# TurquoiseBicuspidProgrammer.net
KiCad netlist of a schematic drawn in EAGLE
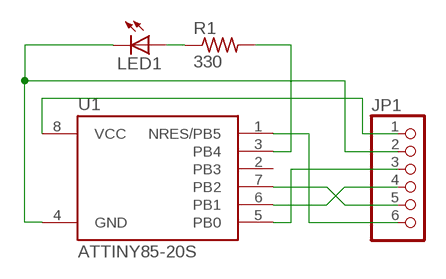
[diagram p0: schematic, sheet 1]

(export (version "E")
  (design (tool "Eeschema 10.0.6"))
  (components
    (comp (ref "JP1")
      (value "PINHD-1X6")
      (footprint "eagle-import:1X06")
      (libsource (lib "eagle-import") (part "PINHD-1X6"))
    )
    (comp (ref "LED1")
      (value "LED5MM")
      (footprint "eagle-import:LED5MM")
      (libsource (lib "eagle-import") (part "LED5MM"))
    )
    (comp (ref "R1")
      (value "330")
      (footprint "eagle-import:0207_10")
      (libsource (lib "eagle-import") (part "R-US_0207/10"))
    )
    (comp (ref "U1")
      (value "ATTINY85-20S")
      (footprint "eagle-import:SOIC8_EIAJ_208MIL")
      (libsource (lib "eagle-import") (part "ATTINY85S-20"))
    )
  )
  (nets
    (net (code "1") (name "Net-(LED1-C)") (class "Default")
      (node (ref "JP1") (pin "2") (pinfunction "2_2") (pintype "passive"))
      (node (ref "LED1") (pin "K") (pinfunction "C_K") (pintype "passive"))
      (node (ref "U1") (pin "4") (pinfunction "GND_4") (pintype "power_in"))
    )
    (net (code "2") (name "Net-(LED1-PadA)") (class "Default")
      (node (ref "LED1") (pin "A") (pinfunction "A_A") (pintype "passive"))
      (node (ref "R1") (pin "1") (pinfunction "1_1") (pintype "passive"))
    )
    (net (code "3") (name "Net-(U1-NRES{slash}PB5)") (class "Default")
      (node (ref "JP1") (pin "6") (pinfunction "6_6") (pintype "passive"))
      (node (ref "U1") (pin "1") (pinfunction "NRES/PB5_1") (pintype "bidirectional"))
    )
    (net (code "4") (name "Net-(U1-PB0)") (class "Default")
      (node (ref "JP1") (pin "3") (pinfunction "3_3") (pintype "passive"))
      (node (ref "U1") (pin "5") (pinfunction "PB0_5") (pintype "bidirectional"))
    )
    (net (code "5") (name "Net-(U1-PB1)") (class "Default")
      (node (ref "JP1") (pin "4") (pinfunction "4_4") (pintype "passive"))
      (node (ref "U1") (pin "6") (pinfunction "PB1_6") (pintype "bidirectional"))
    )
    (net (code "6") (name "Net-(U1-PB2)") (class "Default")
      (node (ref "JP1") (pin "5") (pinfunction "5_5") (pintype "passive"))
      (node (ref "U1") (pin "7") (pinfunction "PB2_7") (pintype "bidirectional"))
    )
    (net (code "7") (name "Net-(U1-PB4)") (class "Default")
      (node (ref "R1") (pin "2") (pinfunction "2_2") (pintype "passive"))
      (node (ref "U1") (pin "3") (pinfunction "PB4_3") (pintype "bidirectional"))
    )
    (net (code "8") (name "Net-(U1-VCC)") (class "Default")
      (node (ref "JP1") (pin "1") (pinfunction "1_1") (pintype "passive"))
      (node (ref "U1") (pin "8") (pinfunction "VCC_8") (pintype "power_in"))
    )
    (net (code "9") (name "unconnected-(U1-PB3-Pad2)") (class "Default")
      (node (ref "U1") (pin "2") (pinfunction "PB3_2") (pintype "bidirectional"))
    )
  )
)
